# LVDS.net
KiCad netlist of a schematic drawn in Altium Designer
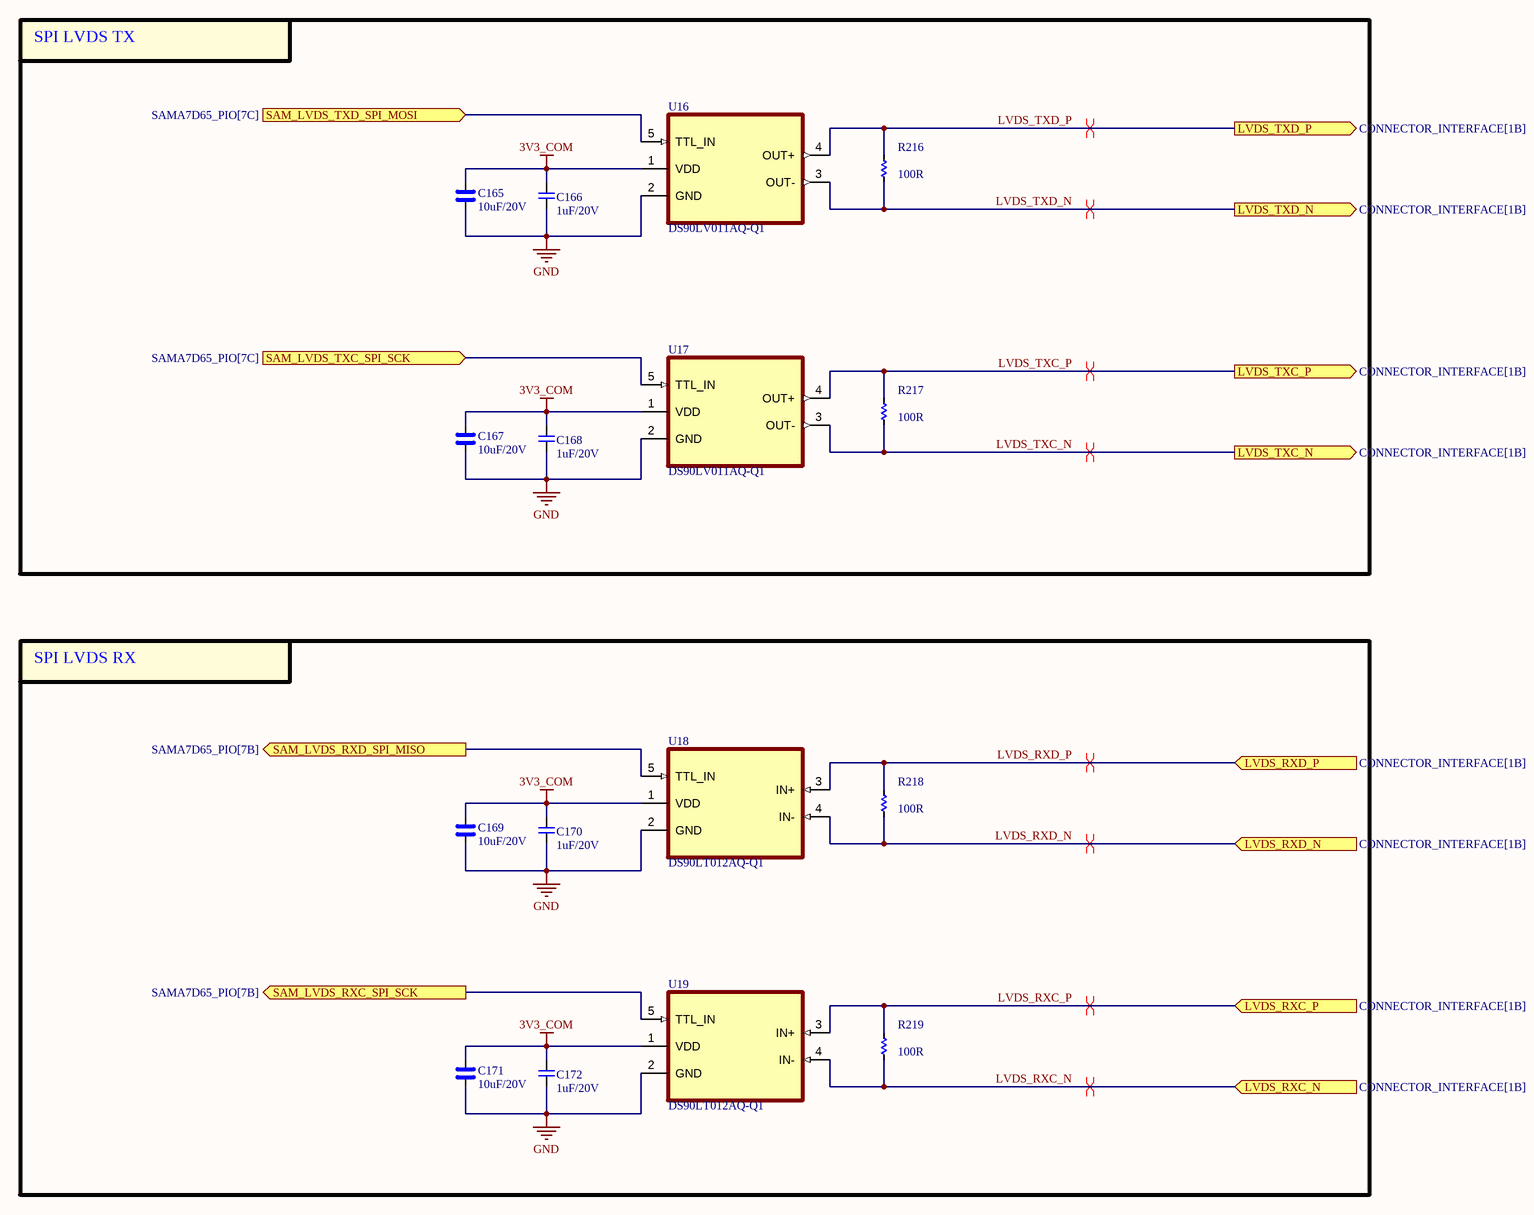
[diagram p0: LVDS.SchDoc]

(export (version "E")
  (design (tool "Eeschema 10.0.6"))
  (components
    (comp (ref "C165")
      (value "10uF/20V")
      (footprint "CAP_C_2012X110")
      (description "CAP CHIP High Value")
      (libsource (lib "IFBschelib") (part "_CAP_C_High_2"))
    )
    (comp (ref "C166")
      (value "1uF/20V")
      (footprint "CAP_C_1005X50_L")
      (description "CAP CHIP")
      (libsource (lib "IFBschelib") (part "_CAP_C_2"))
    )
    (comp (ref "C167")
      (value "10uF/20V")
      (footprint "CAP_C_2012X110")
      (description "CAP CHIP High Value")
      (libsource (lib "IFBschelib") (part "_CAP_C_High_2"))
    )
    (comp (ref "C168")
      (value "1uF/20V")
      (footprint "CAP_C_1005X50_L")
      (description "CAP CHIP")
      (libsource (lib "IFBschelib") (part "_CAP_C_2"))
    )
    (comp (ref "C169")
      (value "10uF/20V")
      (footprint "CAP_C_2012X110")
      (description "CAP CHIP High Value")
      (libsource (lib "IFBschelib") (part "_CAP_C_High_2"))
    )
    (comp (ref "C170")
      (value "1uF/20V")
      (footprint "CAP_C_1005X50_L")
      (description "CAP CHIP")
      (libsource (lib "IFBschelib") (part "_CAP_C_2"))
    )
    (comp (ref "C171")
      (value "10uF/20V")
      (footprint "CAP_C_2012X110")
      (description "CAP CHIP High Value")
      (libsource (lib "IFBschelib") (part "_CAP_C_High_2"))
    )
    (comp (ref "C172")
      (value "1uF/20V")
      (footprint "CAP_C_1005X50_L")
      (description "CAP CHIP")
      (libsource (lib "IFBschelib") (part "_CAP_C_2"))
    )
    (comp (ref "R216")
      (value "100R")
      (footprint "RES_C_1005x30_L")
      (description "RES")
      (libsource (lib "IFBschelib") (part "_RES_B_2"))
    )
    (comp (ref "R217")
      (value "100R")
      (footprint "RES_C_1005x30_L")
      (description "RES")
      (libsource (lib "IFBschelib") (part "_RES_B_2"))
    )
    (comp (ref "R218")
      (value "100R")
      (footprint "RES_C_1005x30_L")
      (description "RES")
      (libsource (lib "IFBschelib") (part "_RES_B_2"))
    )
    (comp (ref "R219")
      (value "100R")
      (footprint "RES_C_1005x30_L")
      (description "RES")
      (libsource (lib "IFBschelib") (part "_RES_B_2"))
    )
    (comp (ref "U16")
      (value "DS90LV011AQ-Q1")
      (footprint "DS90LV011AQ-Q1")
      (description "Automotive LVDS Differential Driver")
      (libsource (lib "IFBschelib") (part "DS90LV011AQ-Q1"))
    )
    (comp (ref "U17")
      (value "DS90LV011AQ-Q1")
      (footprint "DS90LV011AQ-Q1")
      (description "Automotive LVDS Differential Driver")
      (libsource (lib "IFBschelib") (part "DS90LV011AQ-Q1"))
    )
    (comp (ref "U18")
      (value "DS90LT012AQ-Q1")
      (footprint "DS90LV011AQ-Q1")
      (description "Automotive LVDS Differential Line Receiver")
      (libsource (lib "IFBschelib") (part "DS90LT012AQ-Q1"))
    )
    (comp (ref "U19")
      (value "DS90LT012AQ-Q1")
      (footprint "DS90LV011AQ-Q1")
      (description "Automotive LVDS Differential Line Receiver")
      (libsource (lib "IFBschelib") (part "DS90LT012AQ-Q1"))
    )
  )
  (nets
    (net (code "1") (name "/LVDS_RXC_N") (class "Default")
      (node (ref "R219") (pin "2") (pinfunction "2_2") (pintype "passive"))
      (node (ref "U19") (pin "4") (pinfunction "IN-_4") (pintype "input"))
    )
    (net (code "2") (name "/LVDS_RXC_P") (class "Default")
      (node (ref "R219") (pin "1") (pinfunction "1_1") (pintype "passive"))
      (node (ref "U19") (pin "3") (pinfunction "IN+_3") (pintype "input"))
    )
    (net (code "3") (name "/LVDS_RXD_N") (class "Default")
      (node (ref "R218") (pin "2") (pinfunction "2_2") (pintype "passive"))
      (node (ref "U18") (pin "4") (pinfunction "IN-_4") (pintype "input"))
    )
    (net (code "4") (name "/LVDS_RXD_P") (class "Default")
      (node (ref "R218") (pin "1") (pinfunction "1_1") (pintype "passive"))
      (node (ref "U18") (pin "3") (pinfunction "IN+_3") (pintype "input"))
    )
    (net (code "5") (name "/LVDS_TXC_N") (class "Default")
      (node (ref "R217") (pin "2") (pinfunction "2_2") (pintype "passive"))
      (node (ref "U17") (pin "3") (pinfunction "OUT-_3") (pintype "output"))
    )
    (net (code "6") (name "/LVDS_TXC_P") (class "Default")
      (node (ref "R217") (pin "1") (pinfunction "1_1") (pintype "passive"))
      (node (ref "U17") (pin "4") (pinfunction "OUT+_4") (pintype "output"))
    )
    (net (code "7") (name "/LVDS_TXD_N") (class "Default")
      (node (ref "R216") (pin "2") (pinfunction "2_2") (pintype "passive"))
      (node (ref "U16") (pin "3") (pinfunction "OUT-_3") (pintype "output"))
    )
    (net (code "8") (name "/LVDS_TXD_P") (class "Default")
      (node (ref "R216") (pin "1") (pinfunction "1_1") (pintype "passive"))
      (node (ref "U16") (pin "4") (pinfunction "OUT+_4") (pintype "output"))
    )
    (net (code "9") (name "/SAM_LVDS_RXC_SPI_SCK") (class "Default")
      (node (ref "U19") (pin "5") (pinfunction "TTL_IN_5") (pintype "input"))
    )
    (net (code "10") (name "/SAM_LVDS_RXD_SPI_MISO") (class "Default")
      (node (ref "U18") (pin "5") (pinfunction "TTL_IN_5") (pintype "input"))
    )
    (net (code "11") (name "/SAM_LVDS_TXC_SPI_SCK") (class "Default")
      (node (ref "U17") (pin "5") (pinfunction "TTL_IN_5") (pintype "input"))
    )
    (net (code "12") (name "/SAM_LVDS_TXD_SPI_MOSI") (class "Default")
      (node (ref "U16") (pin "5") (pinfunction "TTL_IN_5") (pintype "input"))
    )
    (net (code "13") (name "3V3_COM") (class "Default")
      (node (ref "C165") (pin "2") (pinfunction "2_2") (pintype "passive"))
      (node (ref "C166") (pin "2") (pinfunction "2_2") (pintype "passive"))
      (node (ref "C167") (pin "2") (pinfunction "2_2") (pintype "passive"))
      (node (ref "C168") (pin "2") (pinfunction "2_2") (pintype "passive"))
      (node (ref "C169") (pin "2") (pinfunction "2_2") (pintype "passive"))
      (node (ref "C170") (pin "2") (pinfunction "2_2") (pintype "passive"))
      (node (ref "C171") (pin "2") (pinfunction "2_2") (pintype "passive"))
      (node (ref "C172") (pin "2") (pinfunction "2_2") (pintype "passive"))
      (node (ref "U16") (pin "1") (pinfunction "VDD_1") (pintype "power_in"))
      (node (ref "U17") (pin "1") (pinfunction "VDD_1") (pintype "power_in"))
      (node (ref "U18") (pin "1") (pinfunction "VDD_1") (pintype "power_in"))
      (node (ref "U19") (pin "1") (pinfunction "VDD_1") (pintype "power_in"))
    )
    (net (code "14") (name "GND") (class "Default")
      (node (ref "C165") (pin "1") (pinfunction "1_1") (pintype "passive"))
      (node (ref "C166") (pin "1") (pinfunction "1_1") (pintype "passive"))
      (node (ref "C167") (pin "1") (pinfunction "1_1") (pintype "passive"))
      (node (ref "C168") (pin "1") (pinfunction "1_1") (pintype "passive"))
      (node (ref "C169") (pin "1") (pinfunction "1_1") (pintype "passive"))
      (node (ref "C170") (pin "1") (pinfunction "1_1") (pintype "passive"))
      (node (ref "C171") (pin "1") (pinfunction "1_1") (pintype "passive"))
      (node (ref "C172") (pin "1") (pinfunction "1_1") (pintype "passive"))
      (node (ref "U16") (pin "2") (pinfunction "GND_2") (pintype "power_in"))
      (node (ref "U17") (pin "2") (pinfunction "GND_2") (pintype "power_in"))
      (node (ref "U18") (pin "2") (pinfunction "GND_2") (pintype "power_in"))
      (node (ref "U19") (pin "2") (pinfunction "GND_2") (pintype "power_in"))
    )
  )
)
